# Connectors.net
KiCad netlist of a schematic drawn in Altium Designer
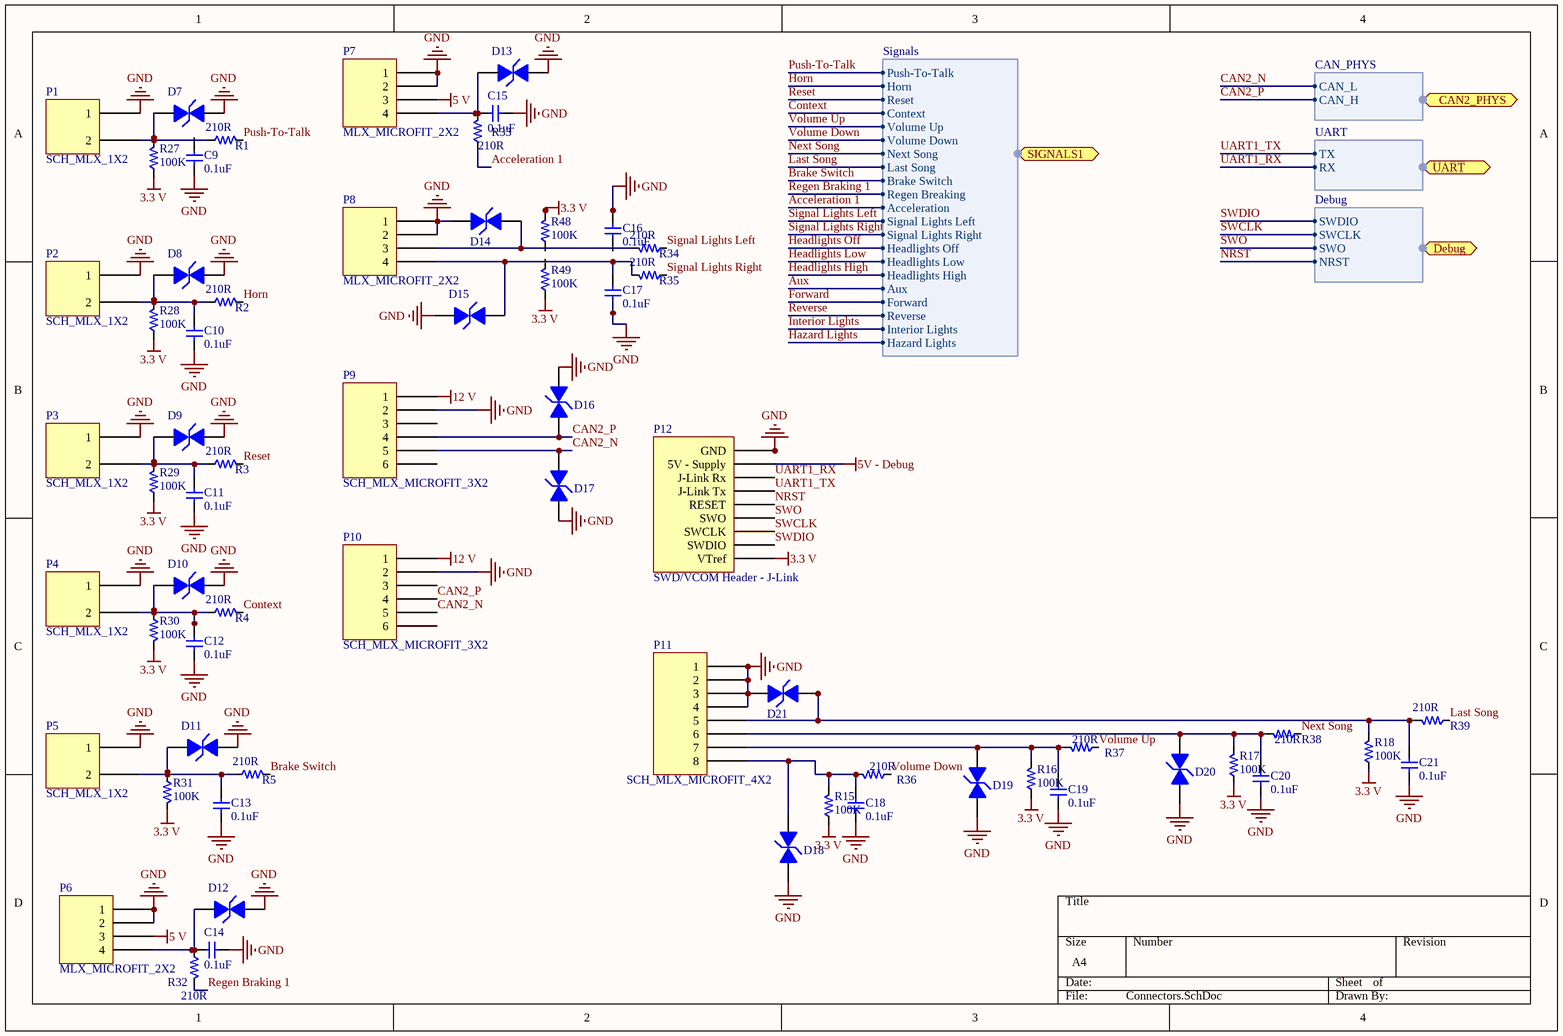
[diagram p0: Connectors.SchDoc]

(export (version "E")
  (design (tool "Eeschema 10.0.6"))
  (components
    (comp (ref "C9")
      (value "0.1uF")
      (footprint "PCB_GENERIC_SMD_0603")
      (description "CAP CER 0603 0.1uF 16V X5R 20%")
      (fields (field (name "TOLERANCE") "20%") (field (name "VOLTAGE") "16V"))
      (libsource (lib "CAP-0603") (part "C060-000U1-00"))
    )
    (comp (ref "C10")
      (value "0.1uF")
      (footprint "PCB_GENERIC_SMD_0603")
      (description "CAP CER 0603 0.1uF 16V X5R 20%")
      (fields (field (name "TOLERANCE") "20%") (field (name "VOLTAGE") "16V"))
      (libsource (lib "CAP-0603") (part "C060-000U1-00"))
    )
    (comp (ref "C11")
      (value "0.1uF")
      (footprint "PCB_GENERIC_SMD_0603")
      (description "CAP CER 0603 0.1uF 16V X5R 20%")
      (fields (field (name "TOLERANCE") "20%") (field (name "VOLTAGE") "16V"))
      (libsource (lib "CAP-0603") (part "C060-000U1-00"))
    )
    (comp (ref "C12")
      (value "0.1uF")
      (footprint "PCB_GENERIC_SMD_0603")
      (description "CAP CER 0603 0.1uF 16V X5R 20%")
      (fields (field (name "TOLERANCE") "20%") (field (name "VOLTAGE") "16V"))
      (libsource (lib "CAP-0603") (part "C060-000U1-00"))
    )
    (comp (ref "C13")
      (value "0.1uF")
      (footprint "PCB_GENERIC_SMD_0603")
      (description "CAP CER 0603 0.1uF 16V X5R 20%")
      (fields (field (name "TOLERANCE") "20%") (field (name "VOLTAGE") "16V"))
      (libsource (lib "CAP-0603") (part "C060-000U1-00"))
    )
    (comp (ref "C14")
      (value "0.1uF")
      (footprint "PCB_GENERIC_SMD_0603")
      (description "CAP CER 0603 0.1uF 16V X5R 20%")
      (fields (field (name "TOLERANCE") "20%") (field (name "VOLTAGE") "16V"))
      (libsource (lib "CAP-0603") (part "C060-000U1-00"))
    )
    (comp (ref "C15")
      (value "0.1uF")
      (footprint "PCB_GENERIC_SMD_0603")
      (description "CAP CER 0603 0.1uF 16V X5R 20%")
      (fields (field (name "TOLERANCE") "20%") (field (name "VOLTAGE") "16V"))
      (libsource (lib "CAP-0603") (part "C060-000U1-00"))
    )
    (comp (ref "C16")
      (value "0.1uF")
      (footprint "PCB_GENERIC_SMD_0603")
      (description "CAP CER 0603 0.1uF 16V X5R 20%")
      (fields (field (name "TOLERANCE") "20%") (field (name "VOLTAGE") "16V"))
      (libsource (lib "CAP-0603") (part "C060-000U1-00"))
    )
    (comp (ref "C17")
      (value "0.1uF")
      (footprint "PCB_GENERIC_SMD_0603")
      (description "CAP CER 0603 0.1uF 16V X5R 20%")
      (fields (field (name "TOLERANCE") "20%") (field (name "VOLTAGE") "16V"))
      (libsource (lib "CAP-0603") (part "C060-000U1-00"))
    )
    (comp (ref "C18")
      (value "0.1uF")
      (footprint "PCB_GENERIC_SMD_0603")
      (description "CAP CER 0603 0.1uF 16V X5R 20%")
      (fields (field (name "TOLERANCE") "20%") (field (name "VOLTAGE") "16V"))
      (libsource (lib "CAP-0603") (part "C060-000U1-00"))
    )
    (comp (ref "C19")
      (value "0.1uF")
      (footprint "PCB_GENERIC_SMD_0603")
      (description "CAP CER 0603 0.1uF 16V X5R 20%")
      (fields (field (name "TOLERANCE") "20%") (field (name "VOLTAGE") "16V"))
      (libsource (lib "CAP-0603") (part "C060-000U1-00"))
    )
    (comp (ref "C20")
      (value "0.1uF")
      (footprint "PCB_GENERIC_SMD_0603")
      (description "CAP CER 0603 0.1uF 16V X5R 20%")
      (fields (field (name "TOLERANCE") "20%") (field (name "VOLTAGE") "16V"))
      (libsource (lib "CAP-0603") (part "C060-000U1-00"))
    )
    (comp (ref "C21")
      (value "0.1uF")
      (footprint "PCB_GENERIC_SMD_0603")
      (description "CAP CER 0603 0.1uF 16V X5R 20%")
      (fields (field (name "TOLERANCE") "20%") (field (name "VOLTAGE") "16V"))
      (libsource (lib "CAP-0603") (part "C060-000U1-00"))
    )
    (comp (ref "D7")
      (value "TVS Diode")
      (footprint "TVS Diode")
      (fields (field (name "MANUFACTURER") "Bourns"))
      (libsource (lib "TVS Diode") (part "TVS Diode"))
    )
    (comp (ref "D8")
      (value "TVS Diode")
      (footprint "TVS Diode")
      (fields (field (name "MANUFACTURER") "Bourns"))
      (libsource (lib "TVS Diode") (part "TVS Diode"))
    )
    (comp (ref "D9")
      (value "TVS Diode")
      (footprint "TVS Diode")
      (fields (field (name "MANUFACTURER") "Bourns"))
      (libsource (lib "TVS Diode") (part "TVS Diode"))
    )
    (comp (ref "D10")
      (value "TVS Diode")
      (footprint "TVS Diode")
      (fields (field (name "MANUFACTURER") "Bourns"))
      (libsource (lib "TVS Diode") (part "TVS Diode"))
    )
    (comp (ref "D11")
      (value "TVS Diode")
      (footprint "TVS Diode")
      (fields (field (name "MANUFACTURER") "Bourns"))
      (libsource (lib "TVS Diode") (part "TVS Diode"))
    )
    (comp (ref "D12")
      (value "TVS Diode")
      (footprint "TVS Diode")
      (fields (field (name "MANUFACTURER") "Bourns"))
      (libsource (lib "TVS Diode") (part "TVS Diode"))
    )
    (comp (ref "D13")
      (value "TVS Diode")
      (footprint "TVS Diode")
      (fields (field (name "MANUFACTURER") "Bourns"))
      (libsource (lib "TVS Diode") (part "TVS Diode"))
    )
    (comp (ref "D14")
      (value "TVS Diode")
      (footprint "TVS Diode")
      (fields (field (name "MANUFACTURER") "Bourns"))
      (libsource (lib "TVS Diode") (part "TVS Diode"))
    )
    (comp (ref "D15")
      (value "TVS Diode")
      (footprint "TVS Diode")
      (fields (field (name "MANUFACTURER") "Bourns"))
      (libsource (lib "TVS Diode") (part "TVS Diode"))
    )
    (comp (ref "D16")
      (value "TVS Diode")
      (footprint "TVS Diode")
      (fields (field (name "MANUFACTURER") "Bourns"))
      (libsource (lib "TVS Diode") (part "TVS Diode"))
    )
    (comp (ref "D17")
      (value "TVS Diode")
      (footprint "TVS Diode")
      (fields (field (name "MANUFACTURER") "Bourns"))
      (libsource (lib "TVS Diode") (part "TVS Diode"))
    )
    (comp (ref "D18")
      (value "TVS Diode")
      (footprint "TVS Diode")
      (fields (field (name "MANUFACTURER") "Bourns"))
      (libsource (lib "TVS Diode") (part "TVS Diode"))
    )
    (comp (ref "D19")
      (value "TVS Diode")
      (footprint "TVS Diode")
      (fields (field (name "MANUFACTURER") "Bourns"))
      (libsource (lib "TVS Diode") (part "TVS Diode"))
    )
    (comp (ref "D20")
      (value "TVS Diode")
      (footprint "TVS Diode")
      (fields (field (name "MANUFACTURER") "Bourns"))
      (libsource (lib "TVS Diode") (part "TVS Diode"))
    )
    (comp (ref "D21")
      (value "TVS Diode")
      (footprint "TVS Diode")
      (fields (field (name "MANUFACTURER") "Bourns"))
      (libsource (lib "TVS Diode") (part "TVS Diode"))
    )
    (comp (ref "P1")
      (value "SCH_MLX_1X2")
      (footprint "PCB_MLX_MICROFIT_1X2")
      (libsource (lib "Molex Microfit 3.0 1x2") (part "SCH_MLX_1X2"))
    )
    (comp (ref "P2")
      (value "SCH_MLX_1X2")
      (footprint "PCB_MLX_MICROFIT_1X2")
      (libsource (lib "Molex Microfit 3.0 1x2") (part "SCH_MLX_1X2"))
    )
    (comp (ref "P3")
      (value "SCH_MLX_1X2")
      (footprint "PCB_MLX_MICROFIT_1X2")
      (libsource (lib "Molex Microfit 3.0 1x2") (part "SCH_MLX_1X2"))
    )
    (comp (ref "P4")
      (value "SCH_MLX_1X2")
      (footprint "PCB_MLX_MICROFIT_1X2")
      (libsource (lib "Molex Microfit 3.0 1x2") (part "SCH_MLX_1X2"))
    )
    (comp (ref "P5")
      (value "SCH_MLX_1X2")
      (footprint "PCB_MLX_MICROFIT_1X2")
      (libsource (lib "Molex Microfit 3.0 1x2") (part "SCH_MLX_1X2"))
    )
    (comp (ref "P6")
      (value "MLX_MICROFIT_2X2")
      (footprint "MLX_MICROFIT_2X2")
      (libsource (lib "Molex Microfit 3.0 2x2") (part "MLX_MICROFIT_2X2"))
    )
    (comp (ref "P7")
      (value "MLX_MICROFIT_2X2")
      (footprint "MLX_MICROFIT_2X2")
      (libsource (lib "Molex Microfit 3.0 2x2") (part "MLX_MICROFIT_2X2"))
    )
    (comp (ref "P8")
      (value "MLX_MICROFIT_2X2")
      (footprint "MLX_MICROFIT_2X2")
      (libsource (lib "Molex Microfit 3.0 2x2") (part "MLX_MICROFIT_2X2"))
    )
    (comp (ref "P9")
      (value "SCH_MLX_MICROFIT_3X2")
      (footprint "Molex Microfit 3.0 3x2:PCB_MLX_MICROFIT_3X2")
      (libsource (lib "Molex Microfit 3.0 3x2") (part "SCH_MLX_MICROFIT_3X2"))
    )
    (comp (ref "P10")
      (value "SCH_MLX_MICROFIT_3X2")
      (footprint "Molex Microfit 3.0 3x2:PCB_MLX_MICROFIT_3X2")
      (libsource (lib "Molex Microfit 3.0 3x2") (part "SCH_MLX_MICROFIT_3X2"))
    )
    (comp (ref "P11")
      (value "SCH_MLX_MICROFIT_4X2")
      (footprint "Molex Microfit 3.0 4x2:PCB_MLX_MICROFIT_4X2")
      (description "Molex Microfit Connector 4x2")
      (libsource (lib "Molex Microfit 3.0 4x2") (part "SCH_MLX_MICROFIT_4X2"))
    )
    (comp (ref "P12")
      (value "SWD/VCOM Header - J-Link")
      (footprint "Samtec TST-110-01-G-D")
      (libsource (lib "Samtec SWD+VCOM Header - J-Link") (part "SWD/VCOM Header"))
    )
    (comp (ref "R1")
      (value "SCH_GENERIC_RESISTOR_0603")
      (footprint "PCB_GENERIC_SMD_0603")
      (description "Generic SMD resistor 0603")
      (fields (field (name "RESISTANCE") "210R"))
      (libsource (lib "Generic 0603 Resistor") (part "SCH_GENERIC_RESISTOR_0603"))
    )
    (comp (ref "R2")
      (value "SCH_GENERIC_RESISTOR_0603")
      (footprint "PCB_GENERIC_SMD_0603")
      (description "Generic SMD resistor 0603")
      (fields (field (name "RESISTANCE") "210R"))
      (libsource (lib "Generic 0603 Resistor") (part "SCH_GENERIC_RESISTOR_0603"))
    )
    (comp (ref "R3")
      (value "SCH_GENERIC_RESISTOR_0603")
      (footprint "PCB_GENERIC_SMD_0603")
      (description "Generic SMD resistor 0603")
      (fields (field (name "RESISTANCE") "210R"))
      (libsource (lib "Generic 0603 Resistor") (part "SCH_GENERIC_RESISTOR_0603"))
    )
    (comp (ref "R4")
      (value "SCH_GENERIC_RESISTOR_0603")
      (footprint "PCB_GENERIC_SMD_0603")
      (description "Generic SMD resistor 0603")
      (fields (field (name "RESISTANCE") "210R"))
      (libsource (lib "Generic 0603 Resistor") (part "SCH_GENERIC_RESISTOR_0603"))
    )
    (comp (ref "R5")
      (value "SCH_GENERIC_RESISTOR_0603")
      (footprint "PCB_GENERIC_SMD_0603")
      (description "Generic SMD resistor 0603")
      (fields (field (name "RESISTANCE") "210R"))
      (libsource (lib "Generic 0603 Resistor") (part "SCH_GENERIC_RESISTOR_0603"))
    )
    (comp (ref "R15")
      (value "100K")
      (footprint "PCB_GENERIC_SMD_0603")
      (description "RES 0603 100K 5% 63mW")
      (fields (field (name "TOLERANCE") "5%") (field (name "POWER") "63mW"))
      (libsource (lib "RES-0603") (part "R060-00104-05"))
    )
    (comp (ref "R16")
      (value "100K")
      (footprint "PCB_GENERIC_SMD_0603")
      (description "RES 0603 100K 5% 63mW")
      (fields (field (name "TOLERANCE") "5%") (field (name "POWER") "63mW"))
      (libsource (lib "RES-0603") (part "R060-00104-05"))
    )
    (comp (ref "R17")
      (value "100K")
      (footprint "PCB_GENERIC_SMD_0603")
      (description "RES 0603 100K 5% 63mW")
      (fields (field (name "TOLERANCE") "5%") (field (name "POWER") "63mW"))
      (libsource (lib "RES-0603") (part "R060-00104-05"))
    )
    (comp (ref "R18")
      (value "100K")
      (footprint "PCB_GENERIC_SMD_0603")
      (description "RES 0603 100K 5% 63mW")
      (fields (field (name "TOLERANCE") "5%") (field (name "POWER") "63mW"))
      (libsource (lib "RES-0603") (part "R060-00104-05"))
    )
    (comp (ref "R27")
      (value "100K")
      (footprint "PCB_GENERIC_SMD_0603")
      (description "RES 0603 100K 5% 63mW")
      (fields (field (name "TOLERANCE") "5%") (field (name "POWER") "63mW"))
      (libsource (lib "RES-0603") (part "R060-00104-05"))
    )
    (comp (ref "R28")
      (value "100K")
      (footprint "PCB_GENERIC_SMD_0603")
      (description "RES 0603 100K 5% 63mW")
      (fields (field (name "TOLERANCE") "5%") (field (name "POWER") "63mW"))
      (libsource (lib "RES-0603") (part "R060-00104-05"))
    )
    (comp (ref "R29")
      (value "100K")
      (footprint "PCB_GENERIC_SMD_0603")
      (description "RES 0603 100K 5% 63mW")
      (fields (field (name "TOLERANCE") "5%") (field (name "POWER") "63mW"))
      (libsource (lib "RES-0603") (part "R060-00104-05"))
    )
    (comp (ref "R30")
      (value "100K")
      (footprint "PCB_GENERIC_SMD_0603")
      (description "RES 0603 100K 5% 63mW")
      (fields (field (name "TOLERANCE") "5%") (field (name "POWER") "63mW"))
      (libsource (lib "RES-0603") (part "R060-00104-05"))
    )
    (comp (ref "R31")
      (value "100K")
      (footprint "PCB_GENERIC_SMD_0603")
      (description "RES 0603 100K 5% 63mW")
      (fields (field (name "TOLERANCE") "5%") (field (name "POWER") "63mW"))
      (libsource (lib "RES-0603") (part "R060-00104-05"))
    )
    (comp (ref "R32")
      (value "SCH_GENERIC_RESISTOR_0603")
      (footprint "PCB_GENERIC_SMD_0603")
      (description "Generic SMD resistor 0603")
      (fields (field (name "RESISTANCE") "210R"))
      (libsource (lib "Generic 0603 Resistor") (part "SCH_GENERIC_RESISTOR_0603"))
    )
    (comp (ref "R33")
      (value "SCH_GENERIC_RESISTOR_0603")
      (footprint "PCB_GENERIC_SMD_0603")
      (description "Generic SMD resistor 0603")
      (fields (field (name "RESISTANCE") "210R"))
      (libsource (lib "Generic 0603 Resistor") (part "SCH_GENERIC_RESISTOR_0603"))
    )
    (comp (ref "R34")
      (value "SCH_GENERIC_RESISTOR_0603")
      (footprint "PCB_GENERIC_SMD_0603")
      (description "Generic SMD resistor 0603")
      (fields (field (name "RESISTANCE") "210R"))
      (libsource (lib "Generic 0603 Resistor") (part "SCH_GENERIC_RESISTOR_0603"))
    )
    (comp (ref "R35")
      (value "SCH_GENERIC_RESISTOR_0603")
      (footprint "PCB_GENERIC_SMD_0603")
      (description "Generic SMD resistor 0603")
      (fields (field (name "RESISTANCE") "210R"))
      (libsource (lib "Generic 0603 Resistor") (part "SCH_GENERIC_RESISTOR_0603"))
    )
    (comp (ref "R36")
      (value "SCH_GENERIC_RESISTOR_0603")
      (footprint "PCB_GENERIC_SMD_0603")
      (description "Generic SMD resistor 0603")
      (fields (field (name "RESISTANCE") "210R"))
      (libsource (lib "Generic 0603 Resistor") (part "SCH_GENERIC_RESISTOR_0603"))
    )
    (comp (ref "R37")
      (value "SCH_GENERIC_RESISTOR_0603")
      (footprint "PCB_GENERIC_SMD_0603")
      (description "Generic SMD resistor 0603")
      (fields (field (name "RESISTANCE") "210R"))
      (libsource (lib "Generic 0603 Resistor") (part "SCH_GENERIC_RESISTOR_0603"))
    )
    (comp (ref "R38")
      (value "SCH_GENERIC_RESISTOR_0603")
      (footprint "PCB_GENERIC_SMD_0603")
      (description "Generic SMD resistor 0603")
      (fields (field (name "RESISTANCE") "210R"))
      (libsource (lib "Generic 0603 Resistor") (part "SCH_GENERIC_RESISTOR_0603"))
    )
    (comp (ref "R39")
      (value "SCH_GENERIC_RESISTOR_0603")
      (footprint "PCB_GENERIC_SMD_0603")
      (description "Generic SMD resistor 0603")
      (fields (field (name "RESISTANCE") "210R"))
      (libsource (lib "Generic 0603 Resistor") (part "SCH_GENERIC_RESISTOR_0603"))
    )
    (comp (ref "R48")
      (value "100K")
      (footprint "PCB_GENERIC_SMD_0603")
      (description "RES 0603 100K 5% 63mW")
      (fields (field (name "TOLERANCE") "5%") (field (name "POWER") "63mW"))
      (libsource (lib "RES-0603") (part "R060-00104-05"))
    )
    (comp (ref "R49")
      (value "100K")
      (footprint "PCB_GENERIC_SMD_0603")
      (description "RES 0603 100K 5% 63mW")
      (fields (field (name "TOLERANCE") "5%") (field (name "POWER") "63mW"))
      (libsource (lib "RES-0603") (part "R060-00104-05"))
    )
  )
  (nets
    (net (code "5") (name "/Acceleration 1") (class "Default")
      (node (ref "R33") (pin "1") (pinfunction "1_1") (pintype "passive"))
    )
    (net (code "7") (name "/Brake Switch") (class "Default")
      (node (ref "R5") (pin "2") (pinfunction "2_2") (pintype "passive"))
    )
    (net (code "8") (name "/CAN2_N") (class "Default")
      (node (ref "D17") (pin "2") (pintype "passive"))
      (node (ref "P10") (pin "5") (pinfunction "5_5") (pintype "passive"))
      (node (ref "P9") (pin "5") (pinfunction "5_5") (pintype "passive"))
    )
    (net (code "9") (name "/CAN2_P") (class "Default")
      (node (ref "D16") (pin "1") (pintype "passive"))
      (node (ref "P10") (pin "4") (pinfunction "4_4") (pintype "passive"))
      (node (ref "P9") (pin "4") (pinfunction "4_4") (pintype "passive"))
    )
    (net (code "10") (name "/Context") (class "Default")
      (node (ref "R4") (pin "2") (pinfunction "2_2") (pintype "passive"))
    )
    (net (code "16") (name "/Horn") (class "Default")
      (node (ref "R2") (pin "2") (pinfunction "2_2") (pintype "passive"))
    )
    (net (code "18") (name "/Last Song") (class "Default")
      (node (ref "R39") (pin "1") (pinfunction "1_1") (pintype "passive"))
    )
    (net (code "19") (name "/NRST") (class "Default")
      (node (ref "P12") (pin "15") (pinfunction "RESET_15") (pintype "passive"))
    )
    (net (code "20") (name "/Next Song") (class "Default")
      (node (ref "R38") (pin "1") (pinfunction "1_1") (pintype "passive"))
    )
    (net (code "21") (name "/Push-To-Talk") (class "Default")
      (node (ref "R1") (pin "2") (pinfunction "2_2") (pintype "passive"))
    )
    (net (code "22") (name "/Regen Braking 1") (class "Default")
      (node (ref "R32") (pin "2") (pinfunction "2_2") (pintype "passive"))
    )
    (net (code "23") (name "/Reset") (class "Default")
      (node (ref "R3") (pin "2") (pinfunction "2_2") (pintype "passive"))
    )
    (net (code "25") (name "/SWCLK") (class "Default")
      (node (ref "P12") (pin "9") (pinfunction "SWCLK_9") (pintype "passive"))
    )
    (net (code "26") (name "/SWDIO") (class "Default")
      (node (ref "P12") (pin "7") (pinfunction "SWDIO_7") (pintype "passive"))
    )
    (net (code "27") (name "/SWO") (class "Default")
      (node (ref "P12") (pin "13") (pinfunction "SWO_13") (pintype "passive"))
    )
    (net (code "28") (name "/Signal Lights Left") (class "Default")
      (node (ref "R34") (pin "1") (pinfunction "1_1") (pintype "passive"))
    )
    (net (code "29") (name "/Signal Lights Right") (class "Default")
      (node (ref "R35") (pin "1") (pinfunction "1_1") (pintype "passive"))
    )
    (net (code "30") (name "/UART1_RX") (class "Default")
      (node (ref "P12") (pin "17") (pinfunction "J-Link_Rx_17") (pintype "passive"))
    )
    (net (code "31") (name "/UART1_TX") (class "Default")
      (node (ref "P12") (pin "5") (pinfunction "J-Link_Tx_5") (pintype "passive"))
    )
    (net (code "32") (name "/Volume Down") (class "Default")
      (node (ref "R36") (pin "1") (pinfunction "1_1") (pintype "passive"))
    )
    (net (code "33") (name "/Volume Up") (class "Default")
      (node (ref "R37") (pin "1") (pinfunction "1_1") (pintype "passive"))
    )
    (net (code "38") (name "3.3 V") (class "Default")
      (node (ref "P12") (pin "1") (pinfunction "VTref_1") (pintype "passive"))
      (node (ref "R17") (pin "1") (pinfunction "1_1") (pintype "passive"))
      (node (ref "R18") (pin "1") (pinfunction "1_1") (pintype "passive"))
      (node (ref "R48") (pin "2") (pinfunction "2_2") (pintype "passive"))
    )
    (net (code "39") (name "5 V") (class "Default")
      (node (ref "P6") (pin "3") (pinfunction "3_3") (pintype "passive"))
      (node (ref "P7") (pin "3") (pinfunction "3_3") (pintype "passive"))
    )
    (net (code "40") (name "5V - Debug") (class "Default")
      (node (ref "P12") (pin "19") (pinfunction "5V_-_Supply_19") (pintype "passive"))
    )
    (net (code "41") (name "12 V") (class "Default")
      (node (ref "P10") (pin "1") (pinfunction "1_1") (pintype "passive"))
      (node (ref "P9") (pin "1") (pinfunction "1_1") (pintype "passive"))
    )
    (net (code "42") (name "GND") (class "Default")
      (node (ref "C16") (pin "1") (pinfunction "1_1") (pintype "passive"))
      (node (ref "C17") (pin "1") (pinfunction "1_1") (pintype "passive"))
      (node (ref "C20") (pin "1") (pinfunction "1_1") (pintype "passive"))
      (node (ref "C21") (pin "1") (pinfunction "1_1") (pintype "passive"))
      (node (ref "D10") (pin "2") (pintype "passive"))
      (node (ref "D11") (pin "2") (pintype "passive"))
      (node (ref "D12") (pin "2") (pintype "passive"))
      (node (ref "D13") (pin "2") (pintype "passive"))
      (node (ref "D14") (pin "1") (pintype "passive"))
      (node (ref "D15") (pin "1") (pintype "passive"))
      (node (ref "D16") (pin "2") (pintype "passive"))
      (node (ref "D17") (pin "1") (pintype "passive"))
      (node (ref "D18") (pin "2") (pintype "passive"))
      (node (ref "D19") (pin "2") (pintype "passive"))
      (node (ref "D20") (pin "2") (pintype "passive"))
      (node (ref "D21") (pin "1") (pintype "passive"))
      (node (ref "D7") (pin "1") (pintype "passive"))
      (node (ref "D8") (pin "2") (pintype "passive"))
      (node (ref "D9") (pin "2") (pintype "passive"))
      (node (ref "P1") (pin "1") (pinfunction "1_1") (pintype "passive"))
      (node (ref "P10") (pin "2") (pinfunction "2_2") (pintype "passive"))
      (node (ref "P11") (pin "1") (pinfunction "1_1") (pintype "passive"))
      (node (ref "P11") (pin "2") (pinfunction "2_2") (pintype "passive"))
      (node (ref "P11") (pin "3") (pinfunction "3_3") (pintype "passive"))
      (node (ref "P11") (pin "4") (pinfunction "4_4") (pintype "passive"))
      (node (ref "P12") (pin "10") (pinfunction "GND_10") (pintype "passive"))
      (node (ref "P12") (pin "12") (pinfunction "GND_12") (pintype "passive"))
      (node (ref "P12") (pin "4") (pinfunction "GND_4") (pintype "passive"))
      (node (ref "P12") (pin "6") (pinfunction "GND_6") (pintype "passive"))
      (node (ref "P12") (pin "8") (pinfunction "GND_8") (pintype "passive"))
      (node (ref "P2") (pin "1") (pinfunction "1_1") (pintype "passive"))
      (node (ref "P3") (pin "1") (pinfunction "1_1") (pintype "passive"))
      (node (ref "P4") (pin "1") (pinfunction "1_1") (pintype "passive"))
      (node (ref "P5") (pin "1") (pinfunction "1_1") (pintype "passive"))
      (node (ref "P6") (pin "1") (pinfunction "1_1") (pintype "passive"))
      (node (ref "P6") (pin "2") (pinfunction "2_2") (pintype "passive"))
      (node (ref "P7") (pin "1") (pinfunction "1_1") (pintype "passive"))
      (node (ref "P7") (pin "2") (pinfunction "2_2") (pintype "passive"))
      (node (ref "P8") (pin "1") (pinfunction "1_1") (pintype "passive"))
      (node (ref "P8") (pin "2") (pinfunction "2_2") (pintype "passive"))
      (node (ref "P9") (pin "2") (pinfunction "2_2") (pintype "passive"))
    )
    (net (code "43") (name "Net-(C10-Pad2)") (class "Default")
      (node (ref "C10") (pin "2") (pinfunction "2_2") (pintype "passive"))
      (node (ref "D8") (pin "1") (pintype "passive"))
      (node (ref "P2") (pin "2") (pinfunction "2_2") (pintype "passive"))
      (node (ref "R2") (pin "1") (pinfunction "1_1") (pintype "passive"))
      (node (ref "R28") (pin "2") (pinfunction "2_2") (pintype "passive"))
    )
    (net (code "44") (name "Net-(C11-Pad2)") (class "Default")
      (node (ref "C11") (pin "2") (pinfunction "2_2") (pintype "passive"))
      (node (ref "D9") (pin "1") (pintype "passive"))
      (node (ref "P3") (pin "2") (pinfunction "2_2") (pintype "passive"))
      (node (ref "R29") (pin "2") (pinfunction "2_2") (pintype "passive"))
      (node (ref "R3") (pin "1") (pinfunction "1_1") (pintype "passive"))
    )
    (net (code "45") (name "Net-(C12-Pad1)") (class "Default")
      (node (ref "C12") (pin "1") (pinfunction "1_1") (pintype "passive"))
      (node (ref "D10") (pin "1") (pintype "passive"))
      (node (ref "P4") (pin "2") (pinfunction "2_2") (pintype "passive"))
      (node (ref "R30") (pin "1") (pinfunction "1_1") (pintype "passive"))
      (node (ref "R4") (pin "1") (pinfunction "1_1") (pintype "passive"))
    )
    (net (code "46") (name "Net-(C13-Pad1)") (class "Default")
      (node (ref "C13") (pin "1") (pinfunction "1_1") (pintype "passive"))
      (node (ref "D11") (pin "1") (pintype "passive"))
      (node (ref "P5") (pin "2") (pinfunction "2_2") (pintype "passive"))
      (node (ref "R31") (pin "1") (pinfunction "1_1") (pintype "passive"))
      (node (ref "R5") (pin "1") (pinfunction "1_1") (pintype "passive"))
    )
    (net (code "47") (name "Net-(C14-Pad1)") (class "Default")
      (node (ref "C14") (pin "1") (pinfunction "1_1") (pintype "passive"))
      (node (ref "D12") (pin "1") (pintype "passive"))
      (node (ref "P6") (pin "4") (pinfunction "4_4") (pintype "passive"))
      (node (ref "R32") (pin "1") (pinfunction "1_1") (pintype "passive"))
    )
    (net (code "48") (name "Net-(C15-Pad2)") (class "Default")
      (node (ref "C15") (pin "2") (pinfunction "2_2") (pintype "passive"))
      (node (ref "D13") (pin "1") (pintype "passive"))
      (node (ref "P7") (pin "4") (pinfunction "4_4") (pintype "passive"))
      (node (ref "R33") (pin "2") (pinfunction "2_2") (pintype "passive"))
    )
    (net (code "49") (name "Net-(C17-Pad2)") (class "Default")
      (node (ref "C17") (pin "2") (pinfunction "2_2") (pintype "passive"))
      (node (ref "D15") (pin "2") (pintype "passive"))
      (node (ref "P8") (pin "4") (pinfunction "4_4") (pintype "passive"))
      (node (ref "R35") (pin "2") (pinfunction "2_2") (pintype "passive"))
    )
    (net (code "50") (name "Net-(C18-Pad2)") (class "Default")
      (node (ref "C18") (pin "2") (pinfunction "2_2") (pintype "passive"))
      (node (ref "D18") (pin "1") (pintype "passive"))
      (node (ref "P11") (pin "8") (pinfunction "8_8") (pintype "passive"))
      (node (ref "R15") (pin "2") (pinfunction "2_2") (pintype "passive"))
      (node (ref "R36") (pin "2") (pinfunction "2_2") (pintype "passive"))
    )
    (net (code "51") (name "Net-(C19-Pad2)") (class "Default")
      (node (ref "C19") (pin "2") (pinfunction "2_2") (pintype "passive"))
      (node (ref "D19") (pin "1") (pintype "passive"))
      (node (ref "P11") (pin "7") (pinfunction "7_7") (pintype "passive"))
      (node (ref "R16") (pin "2") (pinfunction "2_2") (pintype "passive"))
      (node (ref "R37") (pin "2") (pinfunction "2_2") (pintype "passive"))
    )
    (net (code "52") (name "Net-(C20-Pad2)") (class "Default")
      (node (ref "C20") (pin "2") (pinfunction "2_2") (pintype "passive"))
      (node (ref "D20") (pin "1") (pintype "passive"))
      (node (ref "P11") (pin "6") (pinfunction "6_6") (pintype "passive"))
      (node (ref "R17") (pin "2") (pinfunction "2_2") (pintype "passive"))
      (node (ref "R38") (pin "2") (pinfunction "2_2") (pintype "passive"))
    )
    (net (code "53") (name "Net-(C21-Pad2)") (class "Default")
      (node (ref "C21") (pin "2") (pinfunction "2_2") (pintype "passive"))
      (node (ref "D21") (pin "2") (pintype "passive"))
      (node (ref "P11") (pin "5") (pinfunction "5_5") (pintype "passive"))
      (node (ref "R18") (pin "2") (pinfunction "2_2") (pintype "passive"))
      (node (ref "R39") (pin "2") (pinfunction "2_2") (pintype "passive"))
    )
    (net (code "54") (name "Net-(D7-Pad2)") (class "Default")
      (node (ref "D7") (pin "2") (pintype "passive"))
      (node (ref "P1") (pin "2") (pinfunction "2_2") (pintype "passive"))
      (node (ref "R1") (pin "1") (pinfunction "1_1") (pintype "passive"))
      (node (ref "R27") (pin "2") (pinfunction "2_2") (pintype "passive"))
    )
    (net (code "55") (name "Net-(D14-Pad2)") (class "Default")
      (node (ref "D14") (pin "2") (pintype "passive"))
      (node (ref "P8") (pin "3") (pinfunction "3_3") (pintype "passive"))
      (node (ref "R34") (pin "2") (pinfunction "2_2") (pintype "passive"))
    )
    (net (code "56") (name "unconnected-(C9-Pad1)") (class "Default")
      (node (ref "C9") (pin "1") (pinfunction "1_1") (pintype "passive"))
    )
    (net (code "57") (name "unconnected-(C9-Pad2)") (class "Default")
      (node (ref "C9") (pin "2") (pinfunction "2_2") (pintype "passive"))
    )
    (net (code "58") (name "unconnected-(C10-Pad1)") (class "Default")
      (node (ref "C10") (pin "1") (pinfunction "1_1") (pintype "passive"))
    )
    (net (code "59") (name "unconnected-(C11-Pad1)") (class "Default")
      (node (ref "C11") (pin "1") (pinfunction "1_1") (pintype "passive"))
    )
    (net (code "60") (name "unconnected-(C12-Pad2)") (class "Default")
      (node (ref "C12") (pin "2") (pinfunction "2_2") (pintype "passive"))
    )
    (net (code "61") (name "unconnected-(C13-Pad2)") (class "Default")
      (node (ref "C13") (pin "2") (pinfunction "2_2") (pintype "passive"))
    )
    (net (code "62") (name "unconnected-(C14-Pad2)") (class "Default")
      (node (ref "C14") (pin "2") (pinfunction "2_2") (pintype "passive"))
    )
    (net (code "63") (name "unconnected-(C15-Pad1)") (class "Default")
      (node (ref "C15") (pin "1") (pinfunction "1_1") (pintype "passive"))
    )
    (net (code "64") (name "unconnected-(C16-Pad2)") (class "Default")
      (node (ref "C16") (pin "2") (pinfunction "2_2") (pintype "passive"))
    )
    (net (code "65") (name "unconnected-(C18-Pad1)") (class "Default")
      (node (ref "C18") (pin "1") (pinfunction "1_1") (pintype "passive"))
    )
    (net (code "66") (name "unconnected-(C19-Pad1)") (class "Default")
      (node (ref "C19") (pin "1") (pinfunction "1_1") (pintype "passive"))
    )
    (net (code "67") (name "unconnected-(P9-Pad3)") (class "Default")
      (node (ref "P9") (pin "3") (pinfunction "3_3") (pintype "passive"))
    )
    (net (code "68") (name "unconnected-(P9-Pad6)") (class "Default")
      (node (ref "P9") (pin "6") (pinfunction "6_6") (pintype "passive"))
    )
    (net (code "69") (name "unconnected-(P10-Pad3)") (class "Default")
      (node (ref "P10") (pin "3") (pinfunction "3_3") (pintype "passive"))
    )
    (net (code "70") (name "unconnected-(P10-Pad6)") (class "Default")
      (node (ref "P10") (pin "6") (pinfunction "6_6") (pintype "passive"))
    )
    (net (code "71") (name "unconnected-(R15-Pad1)") (class "Default")
      (node (ref "R15") (pin "1") (pinfunction "1_1") (pintype "passive"))
    )
    (net (code "72") (name "unconnected-(R16-Pad1)") (class "Default")
      (node (ref "R16") (pin "1") (pinfunction "1_1") (pintype "passive"))
    )
    (net (code "73") (name "unconnected-(R27-Pad1)") (class "Default")
      (node (ref "R27") (pin "1") (pinfunction "1_1") (pintype "passive"))
    )
    (net (code "74") (name "unconnected-(R28-Pad1)") (class "Default")
      (node (ref "R28") (pin "1") (pinfunction "1_1") (pintype "passive"))
    )
    (net (code "75") (name "unconnected-(R29-Pad1)") (class "Default")
      (node (ref "R29") (pin "1") (pinfunction "1_1") (pintype "passive"))
    )
    (net (code "76") (name "unconnected-(R30-Pad2)") (class "Default")
      (node (ref "R30") (pin "2") (pinfunction "2_2") (pintype "passive"))
    )
    (net (code "77") (name "unconnected-(R31-Pad2)") (class "Default")
      (node (ref "R31") (pin "2") (pinfunction "2_2") (pintype "passive"))
    )
    (net (code "78") (name "unconnected-(R48-Pad1)") (class "Default")
      (node (ref "R48") (pin "1") (pinfunction "1_1") (pintype "passive"))
    )
    (net (code "79") (name "unconnected-(R49-Pad1)") (class "Default")
      (node (ref "R49") (pin "1") (pinfunction "1_1") (pintype "passive"))
    )
    (net (code "80") (name "unconnected-(R49-Pad2)") (class "Default")
      (node (ref "R49") (pin "2") (pinfunction "2_2") (pintype "passive"))
    )
  )
)
